# inopto.net
KiCad netlist of a schematic drawn in Altium Designer
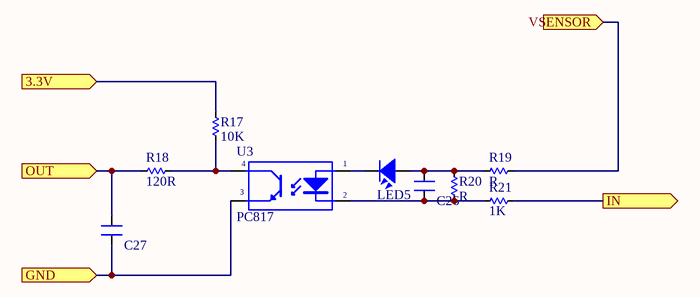
[diagram p0: inopto.SchDoc]

(export (version "E")
  (design (tool "Eeschema 10.0.6"))
  (components
    (comp (ref "C26") (value "CN") (footprint "CN-SMD-0603_big") (libsource (lib "nhan") (part "CN")))
    (comp (ref "C27") (value "CN") (footprint "CN-SMD-0603_big") (libsource (lib "nhan") (part "CN")))
    (comp (ref "LED5")
      (value "MinZ")
      (footprint "LED-0805-Blue")
      (libsource (lib "BanLinhKien") (part "LED SMD"))
    )
    (comp (ref "R17") (value "10K") (footprint "RES-SMD-0603_BIG") (libsource (lib "nhan") (part "R")))
    (comp (ref "R18") (value "120R") (footprint "RES-SMD-0603_BIG") (libsource (lib "nhan") (part "R")))
    (comp (ref "R19") (value "R") (footprint "RES-SMD-0603_BIG") (libsource (lib "nhan") (part "R")))
    (comp (ref "R20") (value "R") (footprint "RES-SMD-0603_BIG") (libsource (lib "nhan") (part "R")))
    (comp (ref "R21") (value "1K") (footprint "RES-SMD-0603_BIG") (libsource (lib "nhan") (part "R")))
    (comp (ref "U3")
      (value "PC817")
      (footprint "PC817SMT")
      (description "Single Opto")
      (libsource (lib "nhan") (part "PC817"))
    )
  )
  (nets
    (net (code "1") (name "/3.3V") (class "Default")
      (node (ref "R17") (pin "1") (pinfunction "1_1") (pintype "passive"))
    )
    (net (code "2") (name "/GND") (class "Default")
      (node (ref "C27") (pin "1") (pinfunction "1_1") (pintype "passive"))
      (node (ref "U3") (pin "3") (pinfunction "E_3") (pintype "passive"))
    )
    (net (code "3") (name "/IN") (class "Default")
      (node (ref "R21") (pin "1") (pinfunction "1_1") (pintype "passive"))
    )
    (net (code "4") (name "/OUT") (class "Default")
      (node (ref "C27") (pin "2") (pinfunction "2_2") (pintype "passive"))
      (node (ref "R18") (pin "1") (pinfunction "1_1") (pintype "passive"))
    )
    (net (code "5") (name "/VSENSOR") (class "Default")
      (node (ref "R19") (pin "1") (pinfunction "1_1") (pintype "passive"))
    )
    (net (code "6") (name "Net-(C26-Pad2)") (class "Default")
      (node (ref "C26") (pin "2") (pinfunction "2_2") (pintype "passive"))
      (node (ref "LED5") (pin "1") (pinfunction "1_1") (pintype "passive"))
      (node (ref "R19") (pin "2") (pinfunction "2_2") (pintype "passive"))
      (node (ref "R20") (pin "1") (pinfunction "1_1") (pintype "passive"))
    )
    (net (code "7") (name "Net-(U3-A)") (class "Default")
      (node (ref "LED5") (pin "2") (pinfunction "2_2") (pintype "passive"))
      (node (ref "U3") (pin "1") (pinfunction "A_1") (pintype "passive"))
    )
    (net (code "8") (name "Net-(U3-C)") (class "Default")
      (node (ref "R17") (pin "2") (pinfunction "2_2") (pintype "passive"))
      (node (ref "R18") (pin "2") (pinfunction "2_2") (pintype "passive"))
      (node (ref "U3") (pin "4") (pinfunction "C_4") (pintype "passive"))
    )
    (net (code "9") (name "Net-(U3-K)") (class "Default")
      (node (ref "C26") (pin "1") (pinfunction "1_1") (pintype "passive"))
      (node (ref "R20") (pin "2") (pinfunction "2_2") (pintype "passive"))
      (node (ref "R21") (pin "2") (pinfunction "2_2") (pintype "passive"))
      (node (ref "U3") (pin "2") (pinfunction "K_2") (pintype "passive"))
    )
  )
)
